# PlacaTestingNov.net
KiCad netlist of a schematic drawn in Altium Designer
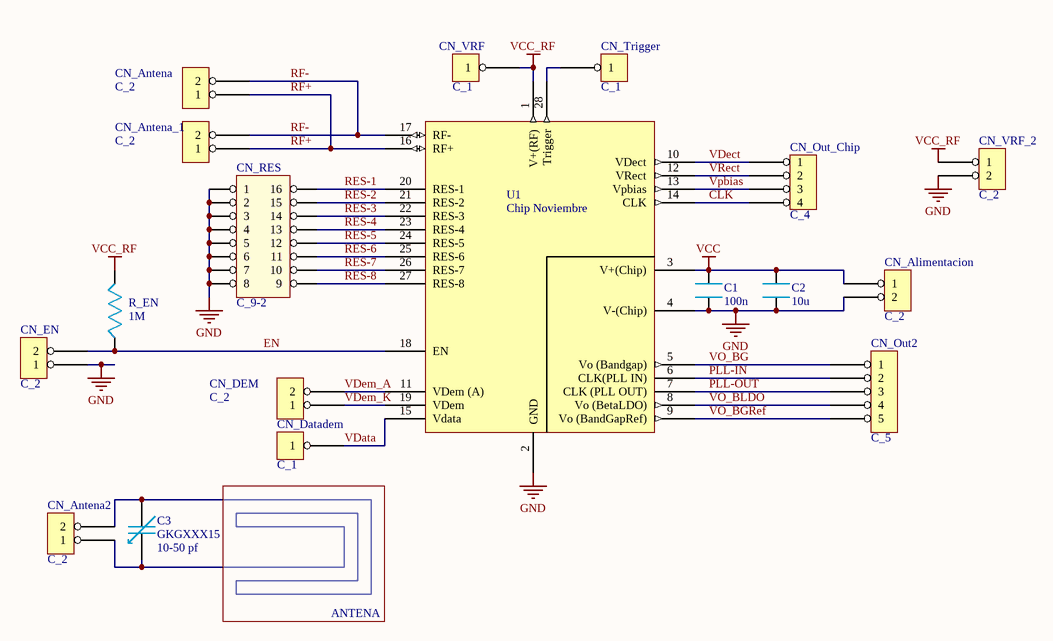
[diagram p0: PlacaTestingNov.SchDoc]

(export (version "E")
  (design (tool "Eeschema 10.0.6"))
  (components
    (comp (ref "C1")
      (value "100n")
      (footprint "2x1 Pin Array")
      (description "Capacitor")
      (libsource (lib "BasicosyConectores") (part "Cap"))
    )
    (comp (ref "C2")
      (value "10u")
      (footprint "GKGXXX15")
      (description "Capacitor")
      (libsource (lib "BasicosyConectores") (part "Cap"))
    )
    (comp (ref "C3")
      (value "GKGXXX15")
      (footprint "GKGXXX15")
      (fields (field (name "C") "10-50 pf"))
      (libsource (lib "GKGXXX15") (part "GKGXXX15"))
    )
    (comp (ref "CN_Alimentacion")
      (value "C_2")
      (footprint "2x1 Bornera")
      (description "Conector 2 pines")
      (libsource (lib "BasicosyConectores") (part "C_2"))
    )
    (comp (ref "CN_Antena")
      (value "C_2")
      (footprint "2x1 Pin Array")
      (description "Conector 2 pines")
      (libsource (lib "") (part "C_2_1"))
    )
    (comp (ref "CN_Antena2")
      (value "C_2")
      (footprint "2x1 Pin Array")
      (description "Conector 2 pines")
      (libsource (lib "") (part "C_2_1"))
    )
    (comp (ref "CN_Antena_1")
      (value "C_2")
      (footprint "2x1 Bornera")
      (description "Conector 2 pines")
      (libsource (lib "") (part "C_2_1"))
    )
    (comp (ref "CN_Datadem")
      (value "C_1")
      (footprint "1x1 Pin Array")
      (description "Conector 1 pines")
      (libsource (lib "BasicosyConectores") (part "C_1"))
    )
    (comp (ref "CN_DEM")
      (value "C_2")
      (footprint "2x1 Pin Array")
      (description "Conector 2 pines")
      (libsource (lib "") (part "C_2_1"))
    )
    (comp (ref "CN_EN")
      (value "C_2")
      (footprint "2x1 Pin Array")
      (description "Conector 2 pines")
      (libsource (lib "") (part "C_2_1"))
    )
    (comp (ref "CN_Out2")
      (value "C_5")
      (footprint "5x1 Pin Array")
      (description "Conector 5 pines")
      (libsource (lib "BasicosyConectores") (part "C_5"))
    )
    (comp (ref "CN_Out_Chip")
      (value "C_4")
      (footprint "4x1 Pin Array")
      (description "Conector 4 pines")
      (libsource (lib "BasicosyConectores") (part "C_4"))
    )
    (comp (ref "CN_RES")
      (value "C_9-2")
      (footprint "PDIP_8")
      (description "Connector 9 pins")
      (libsource (lib "BasicosyConectores") (part "C_9-2"))
    )
    (comp (ref "CN_Trigger")
      (value "C_1")
      (footprint "1x1 Pin Array")
      (description "Conector 1 pines")
      (libsource (lib "") (part "C_1_1"))
    )
    (comp (ref "CN_VRF")
      (value "C_1")
      (footprint "1x1 Pin Array")
      (description "Conector 1 pines")
      (libsource (lib "BasicosyConectores") (part "C_1"))
    )
    (comp (ref "CN_VRF_2")
      (value "C_2")
      (footprint "2x1 Bornera")
      (description "Conector 2 pines")
      (libsource (lib "BasicosyConectores") (part "C_2"))
    )
    (comp (ref "R_EN")
      (value "1M")
      (footprint "R_1/4")
      (description "Chip Resistor")
      (libsource (lib "BasicosyConectores") (part "R"))
    )
    (comp (ref "U1")
      (value "Chip Noviembre")
      (footprint "PDIP_28 - Large")
      (description "UTN 500nm Nativo")
      (fields
        (field (name "MANUFACTURER") "RFID Assembly")
        (field (name "MANUFACTURER PART NUMBER") "Version 1.0omega")
      )
      (libsource (lib "Integrados") (part "Chip Noviembre"))
    )
  )
  (nets
    (net (code "1") (name "/CLK") (class "Default")
      (node (ref "CN_Out_Chip") (pin "4") (pinfunction "4_4") (pintype "passive"))
      (node (ref "U1") (pin "14") (pinfunction "CLK_14") (pintype "output"))
    )
    (net (code "2") (name "/EN") (class "Default")
      (node (ref "CN_EN") (pin "2") (pinfunction "2_2") (pintype "passive"))
      (node (ref "R_EN") (pin "1") (pinfunction "1_1") (pintype "passive"))
      (node (ref "U1") (pin "18") (pinfunction "EN_18") (pintype "power_in"))
    )
    (net (code "3") (name "/PLL-IN") (class "Default")
      (node (ref "CN_Out2") (pin "2") (pinfunction "2_2") (pintype "passive"))
      (node (ref "U1") (pin "6") (pinfunction "CLK(PLL_IN)_6") (pintype "power_in"))
    )
    (net (code "4") (name "/PLL-OUT") (class "Default")
      (node (ref "CN_Out2") (pin "3") (pinfunction "3_3") (pintype "passive"))
      (node (ref "U1") (pin "7") (pinfunction "CLK_(PLL_OUT)_7") (pintype "passive"))
    )
    (net (code "5") (name "/RES-1") (class "Default")
      (node (ref "CN_RES") (pin "16") (pinfunction "16_16") (pintype "passive"))
      (node (ref "U1") (pin "20") (pinfunction "RES-1_20") (pintype "power_in"))
    )
    (net (code "6") (name "/RES-2") (class "Default")
      (node (ref "CN_RES") (pin "15") (pinfunction "15_15") (pintype "passive"))
      (node (ref "U1") (pin "21") (pinfunction "RES-2_21") (pintype "power_in"))
    )
    (net (code "7") (name "/RES-3") (class "Default")
      (node (ref "CN_RES") (pin "14") (pinfunction "14_14") (pintype "passive"))
      (node (ref "U1") (pin "22") (pinfunction "RES-3_22") (pintype "passive"))
    )
    (net (code "8") (name "/RES-4") (class "Default")
      (node (ref "CN_RES") (pin "13") (pinfunction "13_13") (pintype "passive"))
      (node (ref "U1") (pin "23") (pinfunction "RES-4_23") (pintype "power_in"))
    )
    (net (code "9") (name "/RES-5") (class "Default")
      (node (ref "CN_RES") (pin "12") (pinfunction "12_12") (pintype "passive"))
      (node (ref "U1") (pin "24") (pinfunction "RES-5_24") (pintype "power_in"))
    )
    (net (code "10") (name "/RES-6") (class "Default")
      (node (ref "CN_RES") (pin "11") (pinfunction "11_11") (pintype "passive"))
      (node (ref "U1") (pin "25") (pinfunction "RES-6_25") (pintype "power_in"))
    )
    (net (code "11") (name "/RES-7") (class "Default")
      (node (ref "CN_RES") (pin "10") (pinfunction "10_10") (pintype "passive"))
      (node (ref "U1") (pin "26") (pinfunction "RES-7_26") (pintype "passive"))
    )
    (net (code "12") (name "/RES-8") (class "Default")
      (node (ref "CN_RES") (pin "9") (pinfunction "9_9") (pintype "passive"))
      (node (ref "U1") (pin "27") (pinfunction "RES-8_27") (pintype "passive"))
    )
    (net (code "13") (name "/RF+") (class "Default")
      (node (ref "CN_Antena") (pin "1") (pinfunction "1_1") (pintype "passive"))
      (node (ref "CN_Antena_1") (pin "1") (pinfunction "1_1") (pintype "passive"))
      (node (ref "U1") (pin "16") (pinfunction "RF+_16") (pintype "bidirectional"))
    )
    (net (code "14") (name "/RF-") (class "Default")
      (node (ref "CN_Antena") (pin "2") (pinfunction "2_2") (pintype "passive"))
      (node (ref "CN_Antena_1") (pin "2") (pinfunction "2_2") (pintype "passive"))
      (node (ref "U1") (pin "17") (pinfunction "RF-_17") (pintype "bidirectional"))
    )
    (net (code "15") (name "/VData") (class "Default")
      (node (ref "CN_Datadem") (pin "1") (pinfunction "1_1") (pintype "passive"))
      (node (ref "U1") (pin "15") (pinfunction "Vdata_15") (pintype "power_in"))
    )
    (net (code "16") (name "/VDect") (class "Default")
      (node (ref "CN_Out_Chip") (pin "1") (pinfunction "1_1") (pintype "passive"))
      (node (ref "U1") (pin "10") (pinfunction "VDect_10") (pintype "output"))
    )
    (net (code "17") (name "/VDem_A") (class "Default")
      (node (ref "CN_DEM") (pin "2") (pinfunction "2_2") (pintype "passive"))
      (node (ref "U1") (pin "11") (pinfunction "VDem_(A)_11") (pintype "power_in"))
    )
    (net (code "18") (name "/VDem_K") (class "Default")
      (node (ref "CN_DEM") (pin "1") (pinfunction "1_1") (pintype "passive"))
      (node (ref "U1") (pin "19") (pinfunction "VDem_19") (pintype "power_in"))
    )
    (net (code "19") (name "/VO_BG") (class "Default")
      (node (ref "CN_Out2") (pin "1") (pinfunction "1_1") (pintype "passive"))
      (node (ref "U1") (pin "5") (pinfunction "Vo_(Bandgap)_5") (pintype "output"))
    )
    (net (code "20") (name "/VO_BGRef") (class "Default")
      (node (ref "CN_Out2") (pin "5") (pinfunction "5_5") (pintype "passive"))
      (node (ref "U1") (pin "9") (pinfunction "Vo_(BandGapRef)_9") (pintype "output"))
    )
    (net (code "21") (name "/VO_BLDO") (class "Default")
      (node (ref "CN_Out2") (pin "4") (pinfunction "4_4") (pintype "passive"))
      (node (ref "U1") (pin "8") (pinfunction "Vo_(BetaLDO)_8") (pintype "output"))
    )
    (net (code "22") (name "/VRect") (class "Default")
      (node (ref "CN_Out_Chip") (pin "2") (pinfunction "2_2") (pintype "passive"))
      (node (ref "U1") (pin "12") (pinfunction "VRect_12") (pintype "output"))
    )
    (net (code "23") (name "/Vpbias") (class "Default")
      (node (ref "CN_Out_Chip") (pin "3") (pinfunction "3_3") (pintype "passive"))
      (node (ref "U1") (pin "13") (pinfunction "Vpbias_13") (pintype "output"))
    )
    (net (code "24") (name "GND") (class "Default")
      (node (ref "C1") (pin "2") (pinfunction "2_2") (pintype "passive"))
      (node (ref "C2") (pin "2") (pinfunction "2_2") (pintype "passive"))
      (node (ref "CN_Alimentacion") (pin "2") (pinfunction "2_2") (pintype "passive"))
      (node (ref "CN_EN") (pin "1") (pinfunction "1_1") (pintype "passive"))
      (node (ref "CN_RES") (pin "1") (pinfunction "1_1") (pintype "passive"))
      (node (ref "CN_RES") (pin "2") (pinfunction "2_2") (pintype "passive"))
      (node (ref "CN_RES") (pin "3") (pinfunction "3_3") (pintype "passive"))
      (node (ref "CN_RES") (pin "4") (pinfunction "4_4") (pintype "passive"))
      (node (ref "CN_RES") (pin "5") (pinfunction "5_5") (pintype "passive"))
      (node (ref "CN_RES") (pin "6") (pinfunction "6_6") (pintype "passive"))
      (node (ref "CN_RES") (pin "7") (pinfunction "7_7") (pintype "passive"))
      (node (ref "CN_RES") (pin "8") (pinfunction "8_8") (pintype "passive"))
      (node (ref "CN_VRF_2") (pin "2") (pinfunction "2_2") (pintype "passive"))
      (node (ref "U1") (pin "2") (pinfunction "GND_2") (pintype "passive"))
      (node (ref "U1") (pin "4") (pinfunction "V-(Chip)_4") (pintype "passive"))
    )
    (net (code "25") (name "Net-(C3-Pad0)") (class "Default")
      (node (ref "C3") (pin "0") (pinfunction "0_0") (pintype "passive"))
      (node (ref "C3") (pin "1") (pinfunction "1_1") (pintype "passive"))
      (node (ref "CN_Antena2") (pin "1") (pinfunction "1_1") (pintype "passive"))
      (node (ref "CN_Antena2") (pin "2") (pinfunction "2_2") (pintype "passive"))
    )
    (net (code "26") (name "Net-(U1-Trigger)") (class "Default")
      (node (ref "CN_Trigger") (pin "1") (pinfunction "1_1") (pintype "passive"))
      (node (ref "U1") (pin "28") (pinfunction "Trigger_28") (pintype "output"))
    )
    (net (code "27") (name "VCC") (class "Default")
      (node (ref "C1") (pin "1") (pinfunction "1_1") (pintype "passive"))
      (node (ref "C2") (pin "1") (pinfunction "1_1") (pintype "passive"))
      (node (ref "CN_Alimentacion") (pin "1") (pinfunction "1_1") (pintype "passive"))
      (node (ref "U1") (pin "3") (pinfunction "V+(Chip)_3") (pintype "power_in"))
    )
    (net (code "28") (name "VCC_RF") (class "Default")
      (node (ref "CN_VRF") (pin "1") (pinfunction "1_1") (pintype "passive"))
      (node (ref "CN_VRF_2") (pin "1") (pinfunction "1_1") (pintype "passive"))
      (node (ref "R_EN") (pin "2") (pinfunction "2_2") (pintype "passive"))
      (node (ref "U1") (pin "1") (pinfunction "V+(RF)_1") (pintype "output"))
    )
  )
)
